# XP-Hardv_PMU.net
KiCad netlist of a schematic drawn in Altium Designer
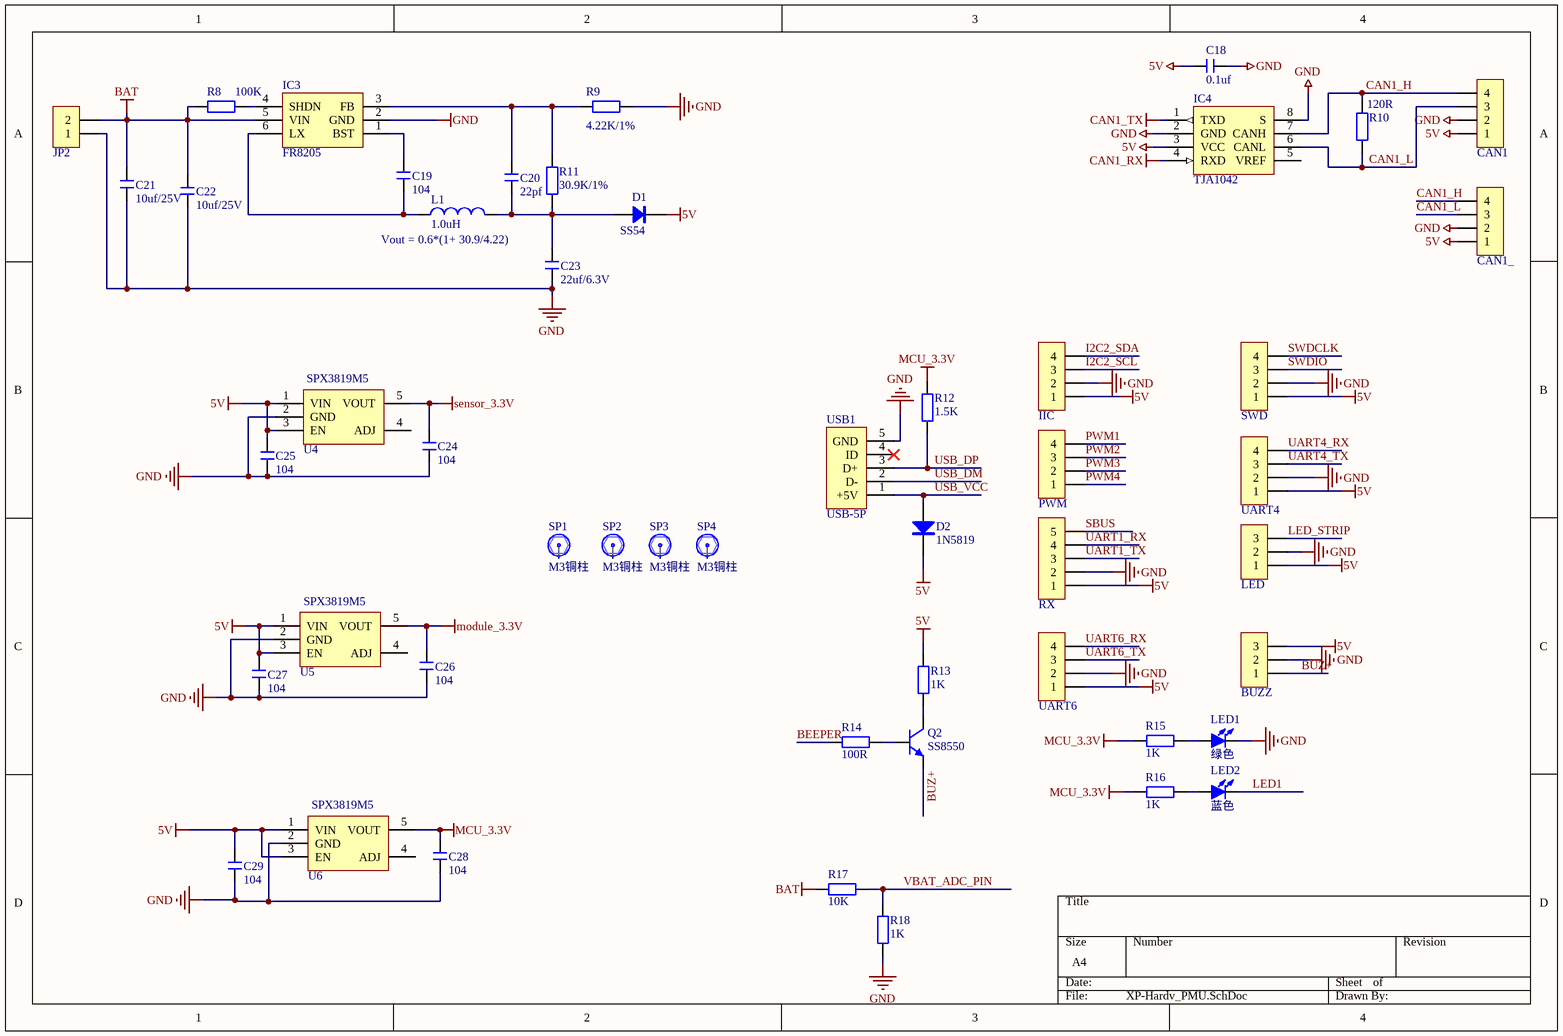
[diagram p0: XP-Hardv_PMU.SchDoc]

(export (version "E")
  (design (tool "Eeschema 10.0.6"))
  (components
    (comp (ref "BUZZ")
      (value "Header 3")
      (footprint "SH1.00-WS-3P")
      (description "3P接插件")
      (fields (field (name "版权所有") "河池学院智能控制重点实验室"))
      (libsource (lib "HCXY_接插件_脚距1.00mm") (part "Header 3"))
    )
    (comp (ref "C18") (value "0.1uf") (footprint "0402-C-1.6*0.5") (libsource (lib "L-电阻电容电感") (part "C")))
    (comp (ref "C19")
      (value "104")
      (footprint "C 0402_M")
      (description "无极性贴片电容")
      (fields (field (name "版权归属") "源创客"))
      (libsource (lib "3.1   - 电阻-电容-电感") (part "C"))
    )
    (comp (ref "C20")
      (value "22pf")
      (footprint "C 0402_M")
      (description "无极性贴片电容")
      (fields (field (name "版权归属") "源创客"))
      (libsource (lib "3.1   - 电阻-电容-电感") (part "C"))
    )
    (comp (ref "C21")
      (value "10uf/25V")
      (footprint "C 0603_L")
      (description "无极性贴片电容")
      (fields (field (name "版权归属") "源创客"))
      (libsource (lib "3.1   - 电阻-电容-电感") (part "C"))
    )
    (comp (ref "C22")
      (value "10uf/25V")
      (footprint "C 0603_L")
      (description "无极性贴片电容")
      (fields (field (name "版权归属") "源创客"))
      (libsource (lib "3.1   - 电阻-电容-电感") (part "C"))
    )
    (comp (ref "C23")
      (value "22uf/6.3V")
      (footprint "C 0603_L")
      (description "无极性贴片电容")
      (fields (field (name "版权归属") "源创客"))
      (libsource (lib "3.1   - 电阻-电容-电感") (part "C"))
    )
    (comp (ref "C24")
      (value "104")
      (footprint "C 0402_M")
      (description "无极性贴片电容")
      (fields (field (name "版权归属") "源创客"))
      (libsource (lib "3.1   - 电阻-电容-电感") (part "C"))
    )
    (comp (ref "C25")
      (value "104")
      (footprint "C 0402_M")
      (description "无极性贴片电容")
      (fields (field (name "版权归属") "源创客"))
      (libsource (lib "3.1   - 电阻-电容-电感") (part "C"))
    )
    (comp (ref "C26")
      (value "104")
      (footprint "C 0402_M")
      (description "无极性贴片电容")
      (fields (field (name "版权归属") "源创客"))
      (libsource (lib "3.1   - 电阻-电容-电感") (part "C"))
    )
    (comp (ref "C27")
      (value "104")
      (footprint "C 0402_M")
      (description "无极性贴片电容")
      (fields (field (name "版权归属") "源创客"))
      (libsource (lib "3.1   - 电阻-电容-电感") (part "C"))
    )
    (comp (ref "C28")
      (value "104")
      (footprint "C 0402_M")
      (description "无极性贴片电容")
      (fields (field (name "版权归属") "源创客"))
      (libsource (lib "3.1   - 电阻-电容-电感") (part "C"))
    )
    (comp (ref "C29")
      (value "104")
      (footprint "C 0402_M")
      (description "无极性贴片电容")
      (fields (field (name "版权归属") "源创客"))
      (libsource (lib "3.1   - 电阻-电容-电感") (part "C"))
    )
    (comp (ref "CAN1")
      (value "Header 4")
      (footprint "SH1.00-WS-4P")
      (description "4P接插件")
      (fields (field (name "版权所有") "河池学院智能控制重点实验室"))
      (libsource (lib "") (part "Header 4_1"))
    )
    (comp (ref "CAN1_")
      (value "Header 4")
      (footprint "SH1.00-WS-4P")
      (description "4P接插件")
      (fields (field (name "版权所有") "河池学院智能控制重点实验室"))
      (libsource (lib "") (part "Header 4_1"))
    )
    (comp (ref "D1")
      (value "SS54")
      (footprint "SMA")
      (description "肖特基二极管")
      (fields (field (name "版权归属") "源创客"))
      (libsource (lib "8.1   - 二极管-整流桥") (part "SS54"))
    )
    (comp (ref "D2")
      (value "1N5819")
      (footprint "SOD-323")
      (description "肖特基二极管")
      (fields (field (name "版权归属") "源创客"))
      (libsource (lib "8.1   - 二极管-整流桥") (part "1N5819"))
    )
    (comp (ref "IC3")
      (value "FR8205")
      (footprint "SOT23-6L")
      (description "可调升压芯片")
      (fields (field (name "版权归属") "源创客"))
      (libsource (lib "1.3   - 电源类芯片") (part "SX1308"))
    )
    (comp (ref "IC4")
      (value "TJA1042")
      (footprint "L - HVSON - 8 - 3*3")
      (description "CAN总线收发芯片")
      (fields (field (name "版权归属") "源创客"))
      (libsource (lib "1.1   - IC芯片") (part "TJA1050"))
    )
    (comp (ref "IIC")
      (value "Header 4")
      (footprint "SH1.00-WS-4P")
      (description "4P接插件")
      (fields (field (name "版权所有") "河池学院智能控制重点实验室"))
      (libsource (lib "HCXY_接插件_脚距1.00mm") (part "Header 4"))
    )
    (comp (ref "JP2")
      (value "HDR-1X2")
      (footprint "HDR2.54-LI-2P")
      (description "2P接插件")
      (fields (field (name "版权归属") "源创客"))
      (libsource (lib "4.6   - 接插件-脚距2.54") (part "Header 2"))
    )
    (comp (ref "L1") (value "1.0uH") (footprint "L - 7X7-F") (libsource (lib "L-电阻电容电感") (part "L")))
    (comp (ref "LED")
      (value "Header 3")
      (footprint "SH1.00-WS-3P")
      (description "3P接插件")
      (fields (field (name "版权所有") "河池学院智能控制重点实验室"))
      (libsource (lib "HCXY_接插件_脚距1.00mm") (part "Header 3"))
    )
    (comp (ref "LED1")
      (value "绿色")
      (footprint "LED 0603G")
      (description "贴片LED")
      (fields (field (name "版权归属") "源创客"))
      (libsource (lib "9.1   - LED") (part "LED-SMD"))
    )
    (comp (ref "LED2")
      (value "蓝色")
      (footprint "LED 0603B")
      (description "贴片LED")
      (fields (field (name "版权归属") "源创客"))
      (libsource (lib "9.1   - LED") (part "LED-SMD"))
    )
    (comp (ref "PWM")
      (value "Header 4")
      (footprint "SH1.00-WS-4P")
      (description "4P接插件")
      (fields (field (name "版权所有") "河池学院智能控制重点实验室"))
      (libsource (lib "HCXY_接插件_脚距1.00mm") (part "Header 4"))
    )
    (comp (ref "Q2")
      (value "SS8550")
      (footprint "SOT23-3M")
      (description "高频放大-NPN型")
      (fields (field (name "版权归属") "源创客"))
      (libsource (lib "6.2   - 三极管") (part "8050-SMD"))
    )
    (comp (ref "R8")
      (value "100K")
      (footprint "R 0402_M")
      (description "贴片电阻")
      (fields (field (name "版权归属") "源创客"))
      (libsource (lib "3.1   - 电阻-电容-电感") (part "R"))
    )
    (comp (ref "R9")
      (value "4.22K/1%")
      (footprint "R 0402_M")
      (description "贴片电阻")
      (fields (field (name "版权归属") "源创客"))
      (libsource (lib "3.1   - 电阻-电容-电感") (part "R"))
    )
    (comp (ref "R10") (value "120R") (footprint "0402-R-1.6*0.5") (libsource (lib "L-电阻电容电感") (part "R")))
    (comp (ref "R11")
      (value "30.9K/1%")
      (footprint "R 0402_M")
      (description "贴片电阻")
      (fields (field (name "版权归属") "源创客"))
      (libsource (lib "3.1   - 电阻-电容-电感") (part "R"))
    )
    (comp (ref "R12")
      (value "1.5K")
      (footprint "R 0402_M")
      (description "贴片电阻")
      (fields (field (name "版权归属") "源创客"))
      (libsource (lib "3.1   - 电阻-电容-电感") (part "R"))
    )
    (comp (ref "R13")
      (value "1K")
      (footprint "R 0402_M")
      (description "贴片电阻")
      (fields (field (name "版权归属") "源创客"))
      (libsource (lib "3.1   - 电阻-电容-电感") (part "R"))
    )
    (comp (ref "R14")
      (value "100R")
      (footprint "R 0402_M")
      (description "贴片电阻")
      (fields (field (name "版权归属") "源创客"))
      (libsource (lib "3.1   - 电阻-电容-电感") (part "R"))
    )
    (comp (ref "R15")
      (value "1K")
      (footprint "R 0402_M")
      (description "贴片电阻")
      (fields (field (name "版权归属") "源创客"))
      (libsource (lib "3.1   - 电阻-电容-电感") (part "R"))
    )
    (comp (ref "R16")
      (value "1K")
      (footprint "R 0402_M")
      (description "贴片电阻")
      (fields (field (name "版权归属") "源创客"))
      (libsource (lib "3.1   - 电阻-电容-电感") (part "R"))
    )
    (comp (ref "R17")
      (value "10K")
      (footprint "R 0402_M")
      (description "贴片电阻")
      (fields (field (name "版权归属") "源创客"))
      (libsource (lib "3.1   - 电阻-电容-电感") (part "R"))
    )
    (comp (ref "R18")
      (value "1K")
      (footprint "R 0402_M")
      (description "贴片电阻")
      (fields (field (name "版权归属") "源创客"))
      (libsource (lib "3.1   - 电阻-电容-电感") (part "R"))
    )
    (comp (ref "RX")
      (value "Header 5")
      (footprint "SH1.00-WS-5P")
      (description "5P接插件")
      (fields (field (name "版权所有") "河池学院智能控制重点实验室"))
      (libsource (lib "L-接插件_脚距1.00mm") (part "Header 5"))
    )
    (comp (ref "SP1")
      (value "M3铜柱")
      (footprint "M3x4+6_L")
      (description "铜柱")
      (fields (field (name "版权归属") "源创客"))
      (libsource (lib "15.1 - 未分类器件") (part "铜柱加头小焊盘"))
    )
    (comp (ref "SP2")
      (value "M3铜柱")
      (footprint "M3x4+6_L")
      (description "铜柱")
      (fields (field (name "版权归属") "源创客"))
      (libsource (lib "15.1 - 未分类器件") (part "铜柱加头小焊盘"))
    )
    (comp (ref "SP3")
      (value "M3铜柱")
      (footprint "M3x4+6_L")
      (description "铜柱")
      (fields (field (name "版权归属") "源创客"))
      (libsource (lib "15.1 - 未分类器件") (part "铜柱加头小焊盘"))
    )
    (comp (ref "SP4")
      (value "M3铜柱")
      (footprint "M3x4+6_L")
      (description "铜柱")
      (fields (field (name "版权归属") "源创客"))
      (libsource (lib "15.1 - 未分类器件") (part "铜柱加头小焊盘"))
    )
    (comp (ref "SWD")
      (value "Header 4")
      (footprint "SH1.00-WS-4P")
      (description "4P接插件")
      (fields (field (name "版权所有") "河池学院智能控制重点实验室"))
      (libsource (lib "HCXY_接插件_脚距1.00mm") (part "Header 4"))
    )
    (comp (ref "U4")
      (value "SPX3819M5")
      (footprint "L - SOT23-5L")
      (fields (field (name "版权所有") "Ly"))
      (libsource (lib "L-电源芯片") (part "SPX3819M5"))
    )
    (comp (ref "U5")
      (value "SPX3819M5")
      (footprint "L - SOT23-5L")
      (fields (field (name "版权所有") "Ly"))
      (libsource (lib "L-电源芯片") (part "SPX3819M5"))
    )
    (comp (ref "U6")
      (value "SPX3819M5")
      (footprint "L - SOT23-5L")
      (fields (field (name "版权所有") "Ly"))
      (libsource (lib "L-电源芯片") (part "SPX3819M5"))
    )
    (comp (ref "UART4")
      (value "Header 4")
      (footprint "SH1.00-WS-4P")
      (description "4P接插件")
      (fields (field (name "版权所有") "河池学院智能控制重点实验室"))
      (libsource (lib "HCXY_接插件_脚距1.00mm") (part "Header 4"))
    )
    (comp (ref "UART6")
      (value "Header 4")
      (footprint "SH1.00-WS-4P")
      (description "4P接插件")
      (fields (field (name "版权所有") "河池学院智能控制重点实验室"))
      (libsource (lib "HCXY_接插件_脚距1.00mm") (part "Header 4"))
    )
    (comp (ref "USB1")
      (value "USB-5P")
      (footprint "USB-MICRO_D")
      (description "微型USB母座")
      (fields (field (name "版权归属") "源创客"))
      (libsource (lib "4.1   - 接口类") (part "USB-5P"))
    )
  )
  (nets
    (net (code "2") (name "/BEEPER") (class "Default")
      (node (ref "R14") (pin "1") (pinfunction "1_1") (pintype "passive"))
    )
    (net (code "3") (name "/BUZ+") (class "Default")
      (node (ref "BUZZ") (pin "1") (pinfunction "1_1") (pintype "passive"))
      (node (ref "Q2") (pin "2") (pinfunction "E_2") (pintype "passive"))
    )
    (net (code "4") (name "/CAN1_H") (class "Default")
      (node (ref "CAN1") (pin "4") (pinfunction "4_4") (pintype "passive"))
      (node (ref "CAN1_") (pin "4") (pinfunction "4_4") (pintype "passive"))
      (node (ref "IC4") (pin "7") (pinfunction "CANH_7") (pintype "passive"))
      (node (ref "R10") (pin "1") (pinfunction "1_1") (pintype "passive"))
    )
    (net (code "5") (name "/CAN1_L") (class "Default")
      (node (ref "CAN1") (pin "3") (pinfunction "3_3") (pintype "passive"))
      (node (ref "CAN1_") (pin "3") (pinfunction "3_3") (pintype "passive"))
      (node (ref "IC4") (pin "6") (pinfunction "CANL_6") (pintype "passive"))
      (node (ref "R10") (pin "2") (pinfunction "2_2") (pintype "passive"))
    )
    (net (code "6") (name "/I2C2_SCL") (class "Default")
      (node (ref "IIC") (pin "3") (pinfunction "3_3") (pintype "passive"))
    )
    (net (code "7") (name "/I2C2_SDA") (class "Default")
      (node (ref "IIC") (pin "4") (pinfunction "4_4") (pintype "passive"))
    )
    (net (code "8") (name "/LED1") (class "Default")
      (node (ref "LED2") (pin "2") (pinfunction "K_2") (pintype "passive"))
    )
    (net (code "9") (name "/LED_STRIP") (class "Default")
      (node (ref "LED") (pin "3") (pinfunction "3_3") (pintype "passive"))
    )
    (net (code "10") (name "/PWM1") (class "Default")
      (node (ref "PWM") (pin "4") (pinfunction "4_4") (pintype "passive"))
    )
    (net (code "11") (name "/PWM2") (class "Default")
      (node (ref "PWM") (pin "3") (pinfunction "3_3") (pintype "passive"))
    )
    (net (code "12") (name "/PWM3") (class "Default")
      (node (ref "PWM") (pin "2") (pinfunction "2_2") (pintype "passive"))
    )
    (net (code "13") (name "/PWM4") (class "Default")
      (node (ref "PWM") (pin "1") (pinfunction "1_1") (pintype "passive"))
    )
    (net (code "14") (name "/SBUS") (class "Default")
      (node (ref "RX") (pin "5") (pinfunction "5_5") (pintype "passive"))
    )
    (net (code "15") (name "/SWDCLK") (class "Default")
      (node (ref "SWD") (pin "4") (pinfunction "4_4") (pintype "passive"))
    )
    (net (code "16") (name "/SWDIO") (class "Default")
      (node (ref "SWD") (pin "3") (pinfunction "3_3") (pintype "passive"))
    )
    (net (code "17") (name "/UART1_RX") (class "Default")
      (node (ref "RX") (pin "4") (pinfunction "4_4") (pintype "passive"))
    )
    (net (code "18") (name "/UART1_TX") (class "Default")
      (node (ref "RX") (pin "3") (pinfunction "3_3") (pintype "passive"))
    )
    (net (code "19") (name "/UART4_RX") (class "Default")
      (node (ref "UART4") (pin "4") (pinfunction "4_4") (pintype "passive"))
    )
    (net (code "20") (name "/UART4_TX") (class "Default")
      (node (ref "UART4") (pin "3") (pinfunction "3_3") (pintype "passive"))
    )
    (net (code "21") (name "/UART6_RX") (class "Default")
      (node (ref "UART6") (pin "4") (pinfunction "4_4") (pintype "passive"))
    )
    (net (code "22") (name "/UART6_TX") (class "Default")
      (node (ref "UART6") (pin "3") (pinfunction "3_3") (pintype "passive"))
    )
    (net (code "23") (name "/USB_DM") (class "Default")
      (node (ref "USB1") (pin "2") (pinfunction "D-_2") (pintype "passive"))
    )
    (net (code "24") (name "/USB_DP") (class "Default")
      (node (ref "R12") (pin "1") (pinfunction "1_1") (pintype "passive"))
      (node (ref "USB1") (pin "3") (pinfunction "D+_3") (pintype "passive"))
    )
    (net (code "25") (name "/USB_VCC") (class "Default")
      (node (ref "D2") (pin "1") (pinfunction "A_1") (pintype "passive"))
      (node (ref "USB1") (pin "1") (pinfunction "+5V_1") (pintype "passive"))
    )
    (net (code "26") (name "/VBAT_ADC_PIN") (class "Default")
      (node (ref "R17") (pin "2") (pinfunction "2_2") (pintype "passive"))
      (node (ref "R18") (pin "2") (pinfunction "2_2") (pintype "passive"))
    )
    (net (code "27") (name "5V") (class "Default")
      (node (ref "BUZZ") (pin "3") (pinfunction "3_3") (pintype "passive"))
      (node (ref "C18") (pin "1") (pinfunction "1_1") (pintype "passive"))
      (node (ref "C25") (pin "2") (pinfunction "2_2") (pintype "passive"))
      (node (ref "C27") (pin "2") (pinfunction "2_2") (pintype "passive"))
      (node (ref "C29") (pin "2") (pinfunction "2_2") (pintype "passive"))
      (node (ref "CAN1") (pin "1") (pinfunction "1_1") (pintype "passive"))
      (node (ref "CAN1_") (pin "1") (pinfunction "1_1") (pintype "passive"))
      (node (ref "D1") (pin "2") (pinfunction "K_2") (pintype "passive"))
      (node (ref "D2") (pin "2") (pinfunction "K_2") (pintype "passive"))
      (node (ref "IC4") (pin "3") (pinfunction "VCC_3") (pintype "passive"))
      (node (ref "IIC") (pin "1") (pinfunction "1_1") (pintype "passive"))
      (node (ref "LED") (pin "1") (pinfunction "1_1") (pintype "passive"))
      (node (ref "R13") (pin "2") (pinfunction "2_2") (pintype "passive"))
      (node (ref "RX") (pin "1") (pinfunction "1_1") (pintype "passive"))
      (node (ref "SWD") (pin "1") (pinfunction "1_1") (pintype "passive"))
      (node (ref "U4") (pin "1") (pinfunction "VIN_1") (pintype "passive"))
      (node (ref "U4") (pin "3") (pinfunction "EN_3") (pintype "passive"))
      (node (ref "U5") (pin "1") (pinfunction "VIN_1") (pintype "passive"))
      (node (ref "U5") (pin "3") (pinfunction "EN_3") (pintype "passive"))
      (node (ref "U6") (pin "1") (pinfunction "VIN_1") (pintype "passive"))
      (node (ref "U6") (pin "3") (pinfunction "EN_3") (pintype "passive"))
      (node (ref "UART4") (pin "1") (pinfunction "1_1") (pintype "passive"))
      (node (ref "UART6") (pin "1") (pinfunction "1_1") (pintype "passive"))
    )
    (net (code "28") (name "BAT") (class "Default")
      (node (ref "C21") (pin "2") (pinfunction "2_2") (pintype "passive"))
      (node (ref "C22") (pin "2") (pinfunction "2_2") (pintype "passive"))
      (node (ref "IC3") (pin "5") (pinfunction "VIN_5") (pintype "passive"))
      (node (ref "JP2") (pin "2") (pinfunction "2_2") (pintype "passive"))
      (node (ref "R17") (pin "1") (pinfunction "1_1") (pintype "passive"))
      (node (ref "R8") (pin "1") (pinfunction "1_1") (pintype "passive"))
    )
    (net (code "29") (name "CAN1_RX") (class "Default")
      (node (ref "IC4") (pin "4") (pinfunction "RXD_4") (pintype "input"))
    )
    (net (code "30") (name "CAN1_TX") (class "Default")
      (node (ref "IC4") (pin "1") (pinfunction "TXD_1") (pintype "output"))
    )
    (net (code "31") (name "GND") (class "Default")
      (node (ref "BUZZ") (pin "2") (pinfunction "2_2") (pintype "passive"))
      (node (ref "C18") (pin "2") (pinfunction "2_2") (pintype "passive"))
      (node (ref "C21") (pin "1") (pinfunction "1_1") (pintype "passive"))
      (node (ref "C22") (pin "1") (pinfunction "1_1") (pintype "passive"))
      (node (ref "C23") (pin "1") (pinfunction "1_1") (pintype "passive"))
      (node (ref "C24") (pin "1") (pinfunction "1_1") (pintype "passive"))
      (node (ref "C25") (pin "1") (pinfunction "1_1") (pintype "passive"))
      (node (ref "C26") (pin "1") (pinfunction "1_1") (pintype "passive"))
      (node (ref "C27") (pin "1") (pinfunction "1_1") (pintype "passive"))
      (node (ref "C28") (pin "1") (pinfunction "1_1") (pintype "passive"))
      (node (ref "C29") (pin "1") (pinfunction "1_1") (pintype "passive"))
      (node (ref "CAN1") (pin "2") (pinfunction "2_2") (pintype "passive"))
      (node (ref "CAN1_") (pin "2") (pinfunction "2_2") (pintype "passive"))
      (node (ref "IC3") (pin "2") (pinfunction "GND_2") (pintype "passive"))
      (node (ref "IC4") (pin "2") (pinfunction "GND_2") (pintype "passive"))
      (node (ref "IC4") (pin "8") (pinfunction "S_8") (pintype "passive"))
      (node (ref "IIC") (pin "2") (pinfunction "2_2") (pintype "passive"))
      (node (ref "JP2") (pin "1") (pinfunction "1_1") (pintype "passive"))
      (node (ref "LED") (pin "2") (pinfunction "2_2") (pintype "passive"))
      (node (ref "LED1") (pin "2") (pinfunction "K_2") (pintype "passive"))
      (node (ref "R18") (pin "1") (pinfunction "1_1") (pintype "passive"))
      (node (ref "R9") (pin "2") (pinfunction "2_2") (pintype "passive"))
      (node (ref "RX") (pin "2") (pinfunction "2_2") (pintype "passive"))
      (node (ref "SWD") (pin "2") (pinfunction "2_2") (pintype "passive"))
      (node (ref "U4") (pin "2") (pinfunction "GND_2") (pintype "passive"))
      (node (ref "U5") (pin "2") (pinfunction "GND_2") (pintype "passive"))
      (node (ref "U6") (pin "2") (pinfunction "GND_2") (pintype "passive"))
      (node (ref "UART4") (pin "2") (pinfunction "2_2") (pintype "passive"))
      (node (ref "UART6") (pin "2") (pinfunction "2_2") (pintype "passive"))
      (node (ref "USB1") (pin "5") (pinfunction "GND_5") (pintype "passive"))
    )
    (net (code "32") (name "MCU_3.3V") (class "Default")
      (node (ref "C28") (pin "2") (pinfunction "2_2") (pintype "passive"))
      (node (ref "R12") (pin "2") (pinfunction "2_2") (pintype "passive"))
      (node (ref "R15") (pin "2") (pinfunction "2_2") (pintype "passive"))
      (node (ref "R16") (pin "2") (pinfunction "2_2") (pintype "passive"))
      (node (ref "U6") (pin "5") (pinfunction "VOUT_5") (pintype "passive"))
    )
    (net (code "33") (name "Net-(D1-A)") (class "Default")
      (node (ref "C20") (pin "2") (pinfunction "2_2") (pintype "passive"))
      (node (ref "C23") (pin "2") (pinfunction "2_2") (pintype "passive"))
      (node (ref "D1") (pin "1") (pinfunction "A_1") (pintype "passive"))
      (node (ref "L1") (pin "2") (pinfunction "2_2") (pintype "passive"))
      (node (ref "R11") (pin "1") (pinfunction "1_1") (pintype "passive"))
    )
    (net (code "34") (name "Net-(IC3-BST)") (class "Default")
      (node (ref "C19") (pin "2") (pinfunction "2_2") (pintype "passive"))
      (node (ref "IC3") (pin "1") (pinfunction "BST_1") (pintype "passive"))
    )
    (net (code "35") (name "Net-(IC3-FB)") (class "Default")
      (node (ref "C20") (pin "1") (pinfunction "1_1") (pintype "passive"))
      (node (ref "IC3") (pin "3") (pinfunction "FB_3") (pintype "passive"))
      (node (ref "R11") (pin "2") (pinfunction "2_2") (pintype "passive"))
      (node (ref "R9") (pin "1") (pinfunction "1_1") (pintype "passive"))
    )
    (net (code "36") (name "Net-(IC3-LX)") (class "Default")
      (node (ref "C19") (pin "1") (pinfunction "1_1") (pintype "passive"))
      (node (ref "IC3") (pin "6") (pinfunction "LX_6") (pintype "passive"))
      (node (ref "L1") (pin "1") (pinfunction "1_1") (pintype "passive"))
    )
    (net (code "37") (name "Net-(IC3-SHDN)") (class "Default")
      (node (ref "IC3") (pin "4") (pinfunction "SHDN_4") (pintype "passive"))
      (node (ref "R8") (pin "2") (pinfunction "2_2") (pintype "passive"))
    )
    (net (code "38") (name "Net-(LED1-A)") (class "Default")
      (node (ref "LED1") (pin "1") (pinfunction "A_1") (pintype "passive"))
      (node (ref "R15") (pin "1") (pinfunction "1_1") (pintype "passive"))
    )
    (net (code "39") (name "Net-(LED2-A)") (class "Default")
      (node (ref "LED2") (pin "1") (pinfunction "A_1") (pintype "passive"))
      (node (ref "R16") (pin "1") (pinfunction "1_1") (pintype "passive"))
    )
    (net (code "40") (name "Net-(Q2-B)") (class "Default")
      (node (ref "Q2") (pin "1") (pinfunction "B_1") (pintype "passive"))
      (node (ref "R14") (pin "2") (pinfunction "2_2") (pintype "passive"))
    )
    (net (code "41") (name "Net-(Q2-C)") (class "Default")
      (node (ref "Q2") (pin "3") (pinfunction "C_3") (pintype "passive"))
      (node (ref "R13") (pin "1") (pinfunction "1_1") (pintype "passive"))
    )
    (net (code "42") (name "module_3.3V") (class "Default")
      (node (ref "C26") (pin "2") (pinfunction "2_2") (pintype "passive"))
      (node (ref "U5") (pin "5") (pinfunction "VOUT_5") (pintype "passive"))
    )
    (net (code "43") (name "sensor_3.3V") (class "Default")
      (node (ref "C24") (pin "2") (pinfunction "2_2") (pintype "passive"))
      (node (ref "U4") (pin "5") (pinfunction "VOUT_5") (pintype "passive"))
    )
    (net (code "44") (name "unconnected-(IC4-VREF-Pad5)") (class "Default")
      (node (ref "IC4") (pin "5") (pinfunction "VREF_5") (pintype "passive"))
    )
    (net (code "45") (name "unconnected-(SP1-Pad1)") (class "Default")
      (node (ref "SP1") (pin "1") (pinfunction "1_1") (pintype "passive"))
    )
    (net (code "46") (name "unconnected-(SP2-Pad1)") (class "Default")
      (node (ref "SP2") (pin "1") (pinfunction "1_1") (pintype "passive"))
    )
    (net (code "47") (name "unconnected-(SP3-Pad1)") (class "Default")
      (node (ref "SP3") (pin "1") (pinfunction "1_1") (pintype "passive"))
    )
    (net (code "48") (name "unconnected-(SP4-Pad1)") (class "Default")
      (node (ref "SP4") (pin "1") (pinfunction "1_1") (pintype "passive"))
    )
    (net (code "49") (name "unconnected-(U4-ADJ-Pad4)") (class "Default")
      (node (ref "U4") (pin "4") (pinfunction "ADJ_4") (pintype "passive"))
    )
    (net (code "50") (name "unconnected-(U5-ADJ-Pad4)") (class "Default")
      (node (ref "U5") (pin "4") (pinfunction "ADJ_4") (pintype "passive"))
    )
    (net (code "51") (name "unconnected-(U6-ADJ-Pad4)") (class "Default")
      (node (ref "U6") (pin "4") (pinfunction "ADJ_4") (pintype "passive"))
    )
    (net (code "52") (name "unconnected-(USB1-ID-Pad4)") (class "Default")
      (node (ref "USB1") (pin "4") (pinfunction "ID_4") (pintype "passive+no_connect"))
    )
  )
)
